# Hammerhead_-_Arduino_Leonardo_Shield_Hea.net
KiCad netlist of a schematic drawn in Altium Designer
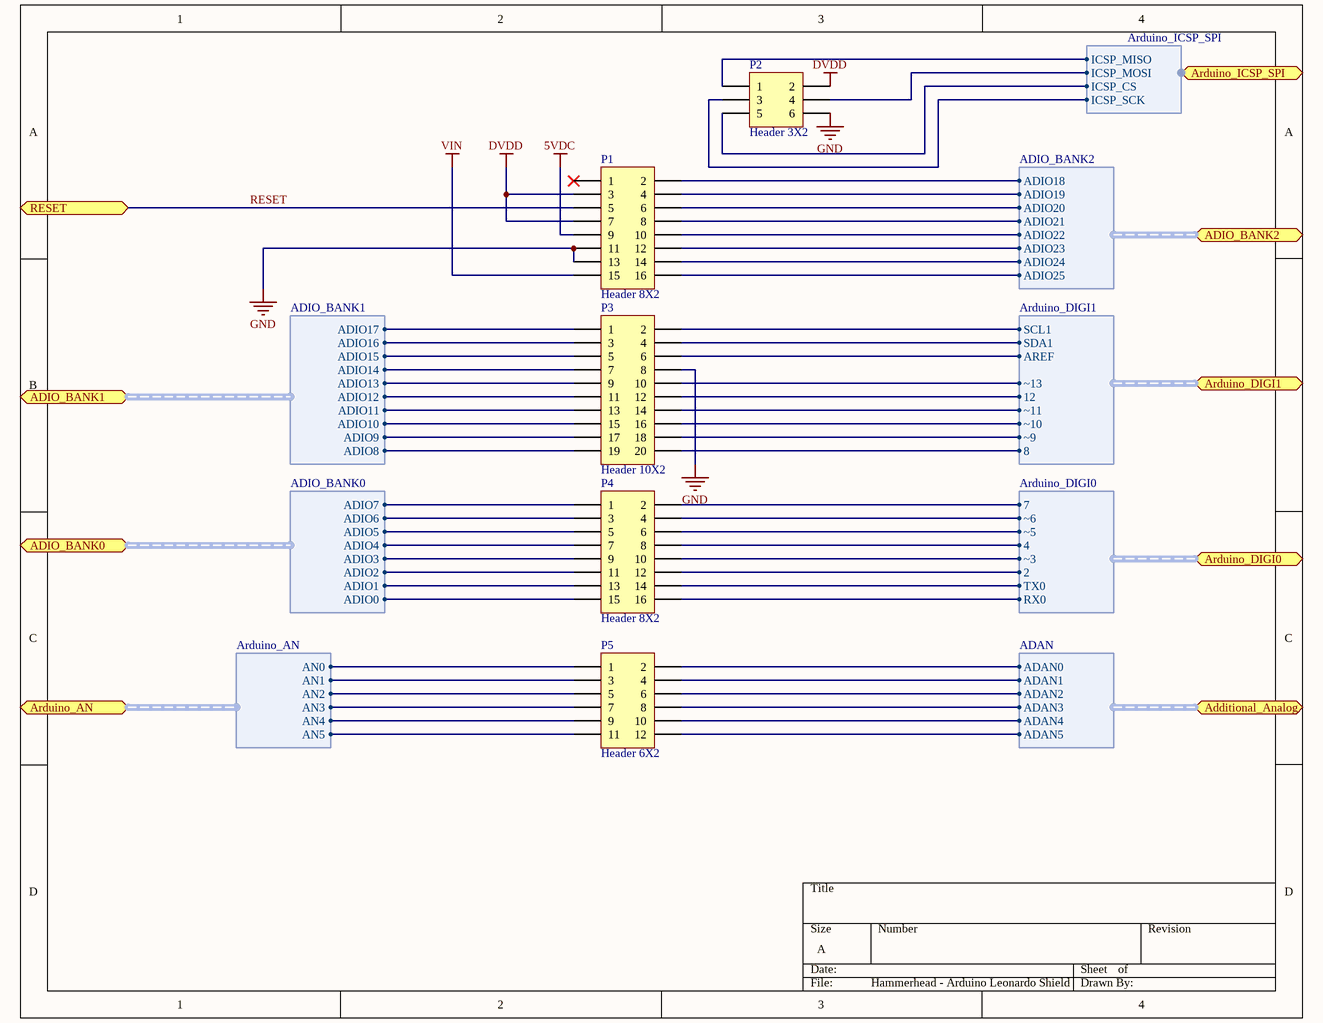
[diagram p0: Hammerhead - Arduino Leonardo Shield Headers R1.1.SchDoc]

(export (version "E")
  (design (tool "Eeschema 10.0.6"))
  (components
    (comp (ref "P1")
      (value "Header 8X2")
      (footprint "HDR2X8")
      (description "Header, 8-Pin, Dual row")
      (fields (field (name "PUBLISHER") "Altium Limited"))
      (libsource (lib "Miscellaneous Connectors") (part "Header 8X2"))
    )
    (comp (ref "P2")
      (value "Header 3X2")
      (footprint "HDR2X3")
      (description "Header, 3-Pin, Dual row")
      (fields (field (name "PUBLISHER") "Altium Limited"))
      (libsource (lib "Miscellaneous Connectors") (part "Header 3X2"))
    )
    (comp (ref "P3")
      (value "Header 10X2")
      (footprint "HDR2X10")
      (description "Header, 10-Pin, Dual row")
      (fields (field (name "PUBLISHER") "Altium Limited"))
      (libsource (lib "Miscellaneous Connectors") (part "Header 10X2"))
    )
    (comp (ref "P4")
      (value "Header 8X2")
      (footprint "HDR2X8")
      (description "Header, 8-Pin, Dual row")
      (fields (field (name "PUBLISHER") "Altium Limited"))
      (libsource (lib "Miscellaneous Connectors") (part "Header 8X2"))
    )
    (comp (ref "P5")
      (value "Header 6X2")
      (footprint "HDR2X6")
      (description "Header, 6-Pin, Dual row")
      (fields (field (name "PUBLISHER") "Altium Limited"))
      (libsource (lib "Miscellaneous Connectors") (part "Header 6X2"))
    )
  )
  (nets
    (net (code "9") (name "/2") (class "Default")
      (node (ref "P4") (pin "12") (pinfunction "12_12") (pintype "passive"))
    )
    (net (code "10") (name "/4") (class "Default")
      (node (ref "P4") (pin "8") (pinfunction "8_8") (pintype "passive"))
    )
    (net (code "11") (name "/7") (class "Default")
      (node (ref "P4") (pin "2") (pinfunction "2_2") (pintype "passive"))
    )
    (net (code "12") (name "/8") (class "Default")
      (node (ref "P3") (pin "20") (pinfunction "20_20") (pintype "passive"))
    )
    (net (code "13") (name "/12") (class "Default")
      (node (ref "P3") (pin "12") (pinfunction "12_12") (pintype "passive"))
    )
    (net (code "14") (name "/ADAN0") (class "Default")
      (node (ref "P5") (pin "2") (pinfunction "2_2") (pintype "passive"))
    )
    (net (code "15") (name "/ADAN1") (class "Default")
      (node (ref "P5") (pin "4") (pinfunction "4_4") (pintype "passive"))
    )
    (net (code "16") (name "/ADAN2") (class "Default")
      (node (ref "P5") (pin "6") (pinfunction "6_6") (pintype "passive"))
    )
    (net (code "17") (name "/ADAN3") (class "Default")
      (node (ref "P5") (pin "8") (pinfunction "8_8") (pintype "passive"))
    )
    (net (code "18") (name "/ADAN4") (class "Default")
      (node (ref "P5") (pin "10") (pinfunction "10_10") (pintype "passive"))
    )
    (net (code "19") (name "/ADAN5") (class "Default")
      (node (ref "P5") (pin "12") (pinfunction "12_12") (pintype "passive"))
    )
    (net (code "20") (name "/ADIO0") (class "Default")
      (node (ref "P4") (pin "15") (pinfunction "15_15") (pintype "passive"))
    )
    (net (code "21") (name "/ADIO1") (class "Default")
      (node (ref "P4") (pin "13") (pinfunction "13_13") (pintype "passive"))
    )
    (net (code "22") (name "/ADIO2") (class "Default")
      (node (ref "P4") (pin "11") (pinfunction "11_11") (pintype "passive"))
    )
    (net (code "23") (name "/ADIO3") (class "Default")
      (node (ref "P4") (pin "9") (pinfunction "9_9") (pintype "passive"))
    )
    (net (code "24") (name "/ADIO4") (class "Default")
      (node (ref "P4") (pin "7") (pinfunction "7_7") (pintype "passive"))
    )
    (net (code "25") (name "/ADIO5") (class "Default")
      (node (ref "P4") (pin "5") (pinfunction "5_5") (pintype "passive"))
    )
    (net (code "26") (name "/ADIO6") (class "Default")
      (node (ref "P4") (pin "3") (pinfunction "3_3") (pintype "passive"))
    )
    (net (code "27") (name "/ADIO7") (class "Default")
      (node (ref "P4") (pin "1") (pinfunction "1_1") (pintype "passive"))
    )
    (net (code "28") (name "/ADIO8") (class "Default")
      (node (ref "P3") (pin "19") (pinfunction "19_19") (pintype "passive"))
    )
    (net (code "29") (name "/ADIO9") (class "Default")
      (node (ref "P3") (pin "17") (pinfunction "17_17") (pintype "passive"))
    )
    (net (code "30") (name "/ADIO10") (class "Default")
      (node (ref "P3") (pin "15") (pinfunction "15_15") (pintype "passive"))
    )
    (net (code "31") (name "/ADIO11") (class "Default")
      (node (ref "P3") (pin "13") (pinfunction "13_13") (pintype "passive"))
    )
    (net (code "32") (name "/ADIO12") (class "Default")
      (node (ref "P3") (pin "11") (pinfunction "11_11") (pintype "passive"))
    )
    (net (code "33") (name "/ADIO13") (class "Default")
      (node (ref "P3") (pin "9") (pinfunction "9_9") (pintype "passive"))
    )
    (net (code "34") (name "/ADIO14") (class "Default")
      (node (ref "P3") (pin "7") (pinfunction "7_7") (pintype "passive"))
    )
    (net (code "35") (name "/ADIO15") (class "Default")
      (node (ref "P3") (pin "5") (pinfunction "5_5") (pintype "passive"))
    )
    (net (code "36") (name "/ADIO16") (class "Default")
      (node (ref "P3") (pin "3") (pinfunction "3_3") (pintype "passive"))
    )
    (net (code "37") (name "/ADIO17") (class "Default")
      (node (ref "P3") (pin "1") (pinfunction "1_1") (pintype "passive"))
    )
    (net (code "38") (name "/ADIO18") (class "Default")
      (node (ref "P1") (pin "2") (pinfunction "2_2") (pintype "passive"))
    )
    (net (code "39") (name "/ADIO19") (class "Default")
      (node (ref "P1") (pin "4") (pinfunction "4_4") (pintype "passive"))
    )
    (net (code "40") (name "/ADIO20") (class "Default")
      (node (ref "P1") (pin "6") (pinfunction "6_6") (pintype "passive"))
    )
    (net (code "41") (name "/ADIO21") (class "Default")
      (node (ref "P1") (pin "8") (pinfunction "8_8") (pintype "passive"))
    )
    (net (code "42") (name "/ADIO22") (class "Default")
      (node (ref "P1") (pin "10") (pinfunction "10_10") (pintype "passive"))
    )
    (net (code "43") (name "/ADIO23") (class "Default")
      (node (ref "P1") (pin "12") (pinfunction "12_12") (pintype "passive"))
    )
    (net (code "44") (name "/ADIO24") (class "Default")
      (node (ref "P1") (pin "14") (pinfunction "14_14") (pintype "passive"))
    )
    (net (code "45") (name "/ADIO25") (class "Default")
      (node (ref "P1") (pin "16") (pinfunction "16_16") (pintype "passive"))
    )
    (net (code "46") (name "/AN0") (class "Default")
      (node (ref "P5") (pin "1") (pinfunction "1_1") (pintype "passive"))
    )
    (net (code "47") (name "/AN1") (class "Default")
      (node (ref "P5") (pin "3") (pinfunction "3_3") (pintype "passive"))
    )
    (net (code "48") (name "/AN2") (class "Default")
      (node (ref "P5") (pin "5") (pinfunction "5_5") (pintype "passive"))
    )
    (net (code "49") (name "/AN3") (class "Default")
      (node (ref "P5") (pin "7") (pinfunction "7_7") (pintype "passive"))
    )
    (net (code "50") (name "/AN4") (class "Default")
      (node (ref "P5") (pin "9") (pinfunction "9_9") (pintype "passive"))
    )
    (net (code "51") (name "/AN5") (class "Default")
      (node (ref "P5") (pin "11") (pinfunction "11_11") (pintype "passive"))
    )
    (net (code "52") (name "/AREF") (class "Default")
      (node (ref "P3") (pin "6") (pinfunction "6_6") (pintype "passive"))
    )
    (net (code "53") (name "/ICSP_CS") (class "Default")
      (node (ref "P2") (pin "5") (pinfunction "5_5") (pintype "passive"))
    )
    (net (code "54") (name "/ICSP_MISO") (class "Default")
      (node (ref "P2") (pin "1") (pinfunction "1_1") (pintype "passive"))
    )
    (net (code "55") (name "/ICSP_MOSI") (class "Default")
      (node (ref "P2") (pin "4") (pinfunction "4_4") (pintype "passive"))
    )
    (net (code "56") (name "/ICSP_SCK") (class "Default")
      (node (ref "P2") (pin "3") (pinfunction "3_3") (pintype "passive"))
    )
    (net (code "57") (name "/RESET") (class "Default")
      (node (ref "P1") (pin "5") (pinfunction "5_5") (pintype "passive"))
    )
    (net (code "58") (name "/RX0") (class "Default")
      (node (ref "P4") (pin "16") (pinfunction "16_16") (pintype "passive"))
    )
    (net (code "59") (name "/SCL1") (class "Default")
      (node (ref "P3") (pin "2") (pinfunction "2_2") (pintype "passive"))
    )
    (net (code "60") (name "/SDA1") (class "Default")
      (node (ref "P3") (pin "4") (pinfunction "4_4") (pintype "passive"))
    )
    (net (code "61") (name "/TX0") (class "Default")
      (node (ref "P4") (pin "14") (pinfunction "14_14") (pintype "passive"))
    )
    (net (code "70") (name "/~3") (class "Default")
      (node (ref "P4") (pin "10") (pinfunction "10_10") (pintype "passive"))
    )
    (net (code "71") (name "/~5") (class "Default")
      (node (ref "P4") (pin "6") (pinfunction "6_6") (pintype "passive"))
    )
    (net (code "72") (name "/~6") (class "Default")
      (node (ref "P4") (pin "4") (pinfunction "4_4") (pintype "passive"))
    )
    (net (code "73") (name "/~9") (class "Default")
      (node (ref "P3") (pin "18") (pinfunction "18_18") (pintype "passive"))
    )
    (net (code "74") (name "/~10") (class "Default")
      (node (ref "P3") (pin "16") (pinfunction "16_16") (pintype "passive"))
    )
    (net (code "75") (name "/~11") (class "Default")
      (node (ref "P3") (pin "14") (pinfunction "14_14") (pintype "passive"))
    )
    (net (code "76") (name "/~13") (class "Default")
      (node (ref "P3") (pin "10") (pinfunction "10_10") (pintype "passive"))
    )
    (net (code "77") (name "5VDC") (class "Default")
      (node (ref "P1") (pin "9") (pinfunction "9_9") (pintype "passive"))
    )
    (net (code "78") (name "DVDD") (class "Default")
      (node (ref "P1") (pin "3") (pinfunction "3_3") (pintype "passive"))
      (node (ref "P1") (pin "7") (pinfunction "7_7") (pintype "passive"))
      (node (ref "P2") (pin "2") (pinfunction "2_2") (pintype "passive"))
    )
    (net (code "79") (name "GND") (class "Default")
      (node (ref "P1") (pin "11") (pinfunction "11_11") (pintype "passive"))
      (node (ref "P1") (pin "13") (pinfunction "13_13") (pintype "passive"))
      (node (ref "P2") (pin "6") (pinfunction "6_6") (pintype "passive"))
      (node (ref "P3") (pin "8") (pinfunction "8_8") (pintype "passive"))
    )
    (net (code "80") (name "VIN") (class "Default")
      (node (ref "P1") (pin "15") (pinfunction "15_15") (pintype "passive"))
    )
    (net (code "81") (name "unconnected-(P1-Pad1)") (class "Default")
      (node (ref "P1") (pin "1") (pinfunction "1_1") (pintype "passive+no_connect"))
    )
  )
)
